# mcu.net
KiCad netlist of a schematic drawn in Altium Designer
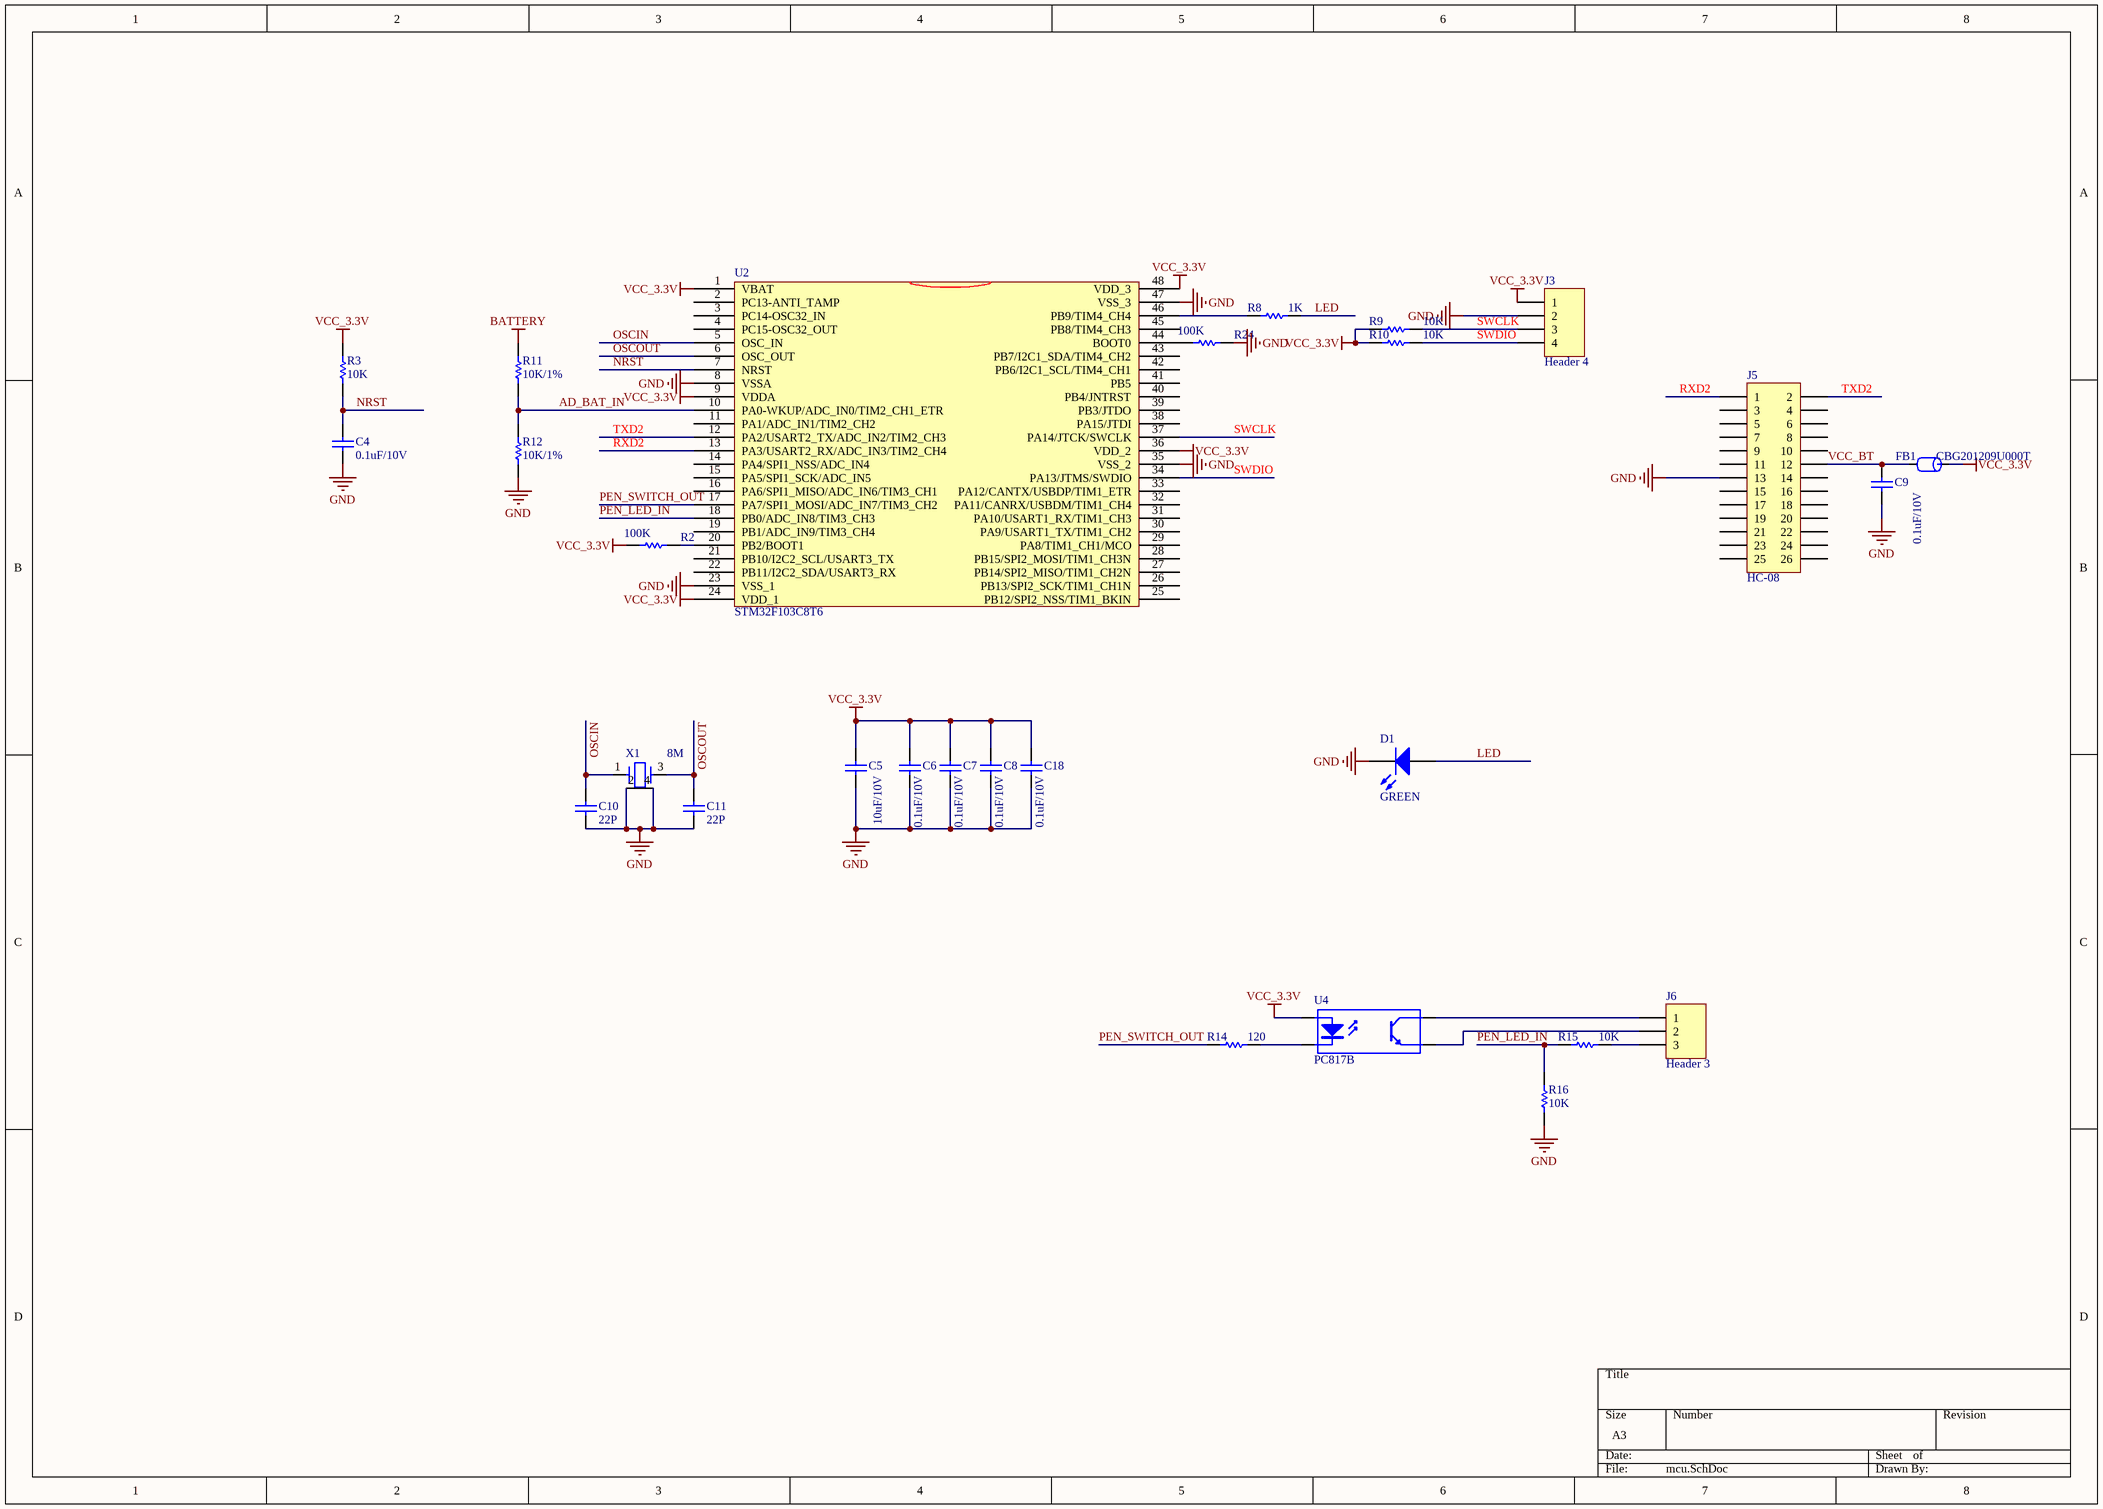
[diagram p0: mcu.SchDoc]

(export (version "E")
  (design (tool "Eeschema 10.0.6"))
  (components
    (comp (ref "C4")
      (value "0.1uF/10V")
      (footprint "0402C")
      (description "Capacitor")
      (fields (field (name "PUBLISHER") "Altium Limited"))
      (libsource (lib "Miscellaneous Devices") (part "Cap"))
    )
    (comp (ref "C5")
      (value "10uF/10V")
      (footprint "0603C")
      (description "Capacitor")
      (fields (field (name "PUBLISHER") "Altium Limited"))
      (libsource (lib "Miscellaneous Devices") (part "Cap"))
    )
    (comp (ref "C6")
      (value "0.1uF/10V")
      (footprint "0402C")
      (description "Capacitor")
      (fields (field (name "PUBLISHER") "Altium Limited"))
      (libsource (lib "Miscellaneous Devices") (part "Cap"))
    )
    (comp (ref "C7")
      (value "0.1uF/10V")
      (footprint "0402C")
      (description "Capacitor")
      (fields (field (name "PUBLISHER") "Altium Limited"))
      (libsource (lib "Miscellaneous Devices") (part "Cap"))
    )
    (comp (ref "C8")
      (value "0.1uF/10V")
      (footprint "0402C")
      (description "Capacitor")
      (fields (field (name "PUBLISHER") "Altium Limited"))
      (libsource (lib "Miscellaneous Devices") (part "Cap"))
    )
    (comp (ref "C9")
      (value "0.1uF/10V")
      (footprint "0402C")
      (description "Capacitor")
      (fields (field (name "PUBLISHER") "Altium Limited"))
      (libsource (lib "Miscellaneous Devices") (part "Cap"))
    )
    (comp (ref "C10")
      (value "22P")
      (footprint "0402C")
      (description "Capacitor")
      (fields (field (name "PUBLISHER") "Altium Limited"))
      (libsource (lib "Miscellaneous Devices") (part "Cap"))
    )
    (comp (ref "C11")
      (value "22P")
      (footprint "0402C")
      (description "Capacitor")
      (fields (field (name "PUBLISHER") "Altium Limited"))
      (libsource (lib "Miscellaneous Devices") (part "Cap"))
    )
    (comp (ref "C18")
      (value "0.1uF/10V")
      (footprint "0402C")
      (description "Capacitor")
      (fields (field (name "PUBLISHER") "Altium Limited"))
      (libsource (lib "Miscellaneous Devices") (part "Cap"))
    )
    (comp (ref "D1")
      (value "~")
      (footprint "0603LED")
      (description "Typical INFRARED GaAs LED")
      (fields (field (name "PUBLISHER") "GREEN"))
      (libsource (lib "Miscellaneous Devices") (part "LED0"))
    )
    (comp (ref "FB1")
      (value "CBG201209U000T")
      (footprint "0805CZ")
      (description "BLM21PG331SN1D")
      (libsource (lib "Schlib_20110825") (part "FB"))
    )
    (comp (ref "J3")
      (value "Header 4")
      (footprint "mHDR1X4")
      (description "Header, 4-Pin")
      (fields (field (name "PUBLISHER") "Altium Limited"))
      (libsource (lib "Miscellaneous Connectors") (part "Header 4"))
    )
    (comp (ref "J5")
      (value "HC-08")
      (footprint "HC-08V20/22/41")
      (description "Header, 13-Pin, Dual row")
      (fields (field (name "PUBLISHER") "Altium Limited"))
      (libsource (lib "Miscellaneous Connectors") (part "Header 13X2"))
    )
    (comp (ref "J6")
      (value "Header 3")
      (footprint "HDR1X3")
      (description "Header, 3-Pin")
      (fields (field (name "PUBLISHER") "Altium Limited"))
      (libsource (lib "Miscellaneous Connectors") (part "Header 3"))
    )
    (comp (ref "R2")
      (value "100K")
      (footprint "0402R")
      (description "Resistor")
      (fields (field (name "PUBLISHER") "Altium Limited"))
      (libsource (lib "Miscellaneous Devices") (part "Res1"))
    )
    (comp (ref "R3")
      (value "10K")
      (footprint "0402R")
      (description "Semiconductor Resistor")
      (fields (field (name "PUBLISHER") "Altium Limited"))
      (libsource (lib "Miscellaneous Devices") (part "Res Semi"))
    )
    (comp (ref "R8")
      (value "1K")
      (footprint "0402R")
      (description "Semiconductor Resistor")
      (fields (field (name "PUBLISHER") "Altium Limited"))
      (libsource (lib "Miscellaneous Devices") (part "Res Semi"))
    )
    (comp (ref "R9")
      (value "10K")
      (footprint "0402R")
      (description "Semiconductor Resistor")
      (fields (field (name "PUBLISHER") "Altium Limited"))
      (libsource (lib "Miscellaneous Devices") (part "Res Semi"))
    )
    (comp (ref "R10")
      (value "10K")
      (footprint "0402R")
      (description "Semiconductor Resistor")
      (fields (field (name "PUBLISHER") "Altium Limited"))
      (libsource (lib "Miscellaneous Devices") (part "Res Semi"))
    )
    (comp (ref "R11")
      (value "10K/1%")
      (footprint "0402R")
      (description "Semiconductor Resistor")
      (fields (field (name "PUBLISHER") "Altium Limited"))
      (libsource (lib "Miscellaneous Devices") (part "Res Semi"))
    )
    (comp (ref "R12")
      (value "10K/1%")
      (footprint "0402R")
      (description "Semiconductor Resistor")
      (fields (field (name "PUBLISHER") "Altium Limited"))
      (libsource (lib "Miscellaneous Devices") (part "Res Semi"))
    )
    (comp (ref "R14")
      (value "120")
      (footprint "0402R")
      (description "Semiconductor Resistor")
      (fields (field (name "PUBLISHER") "Altium Limited"))
      (libsource (lib "Miscellaneous Devices") (part "Res Semi"))
    )
    (comp (ref "R15")
      (value "10K")
      (footprint "0402R")
      (description "Semiconductor Resistor")
      (fields (field (name "PUBLISHER") "Altium Limited"))
      (libsource (lib "Miscellaneous Devices") (part "Res Semi"))
    )
    (comp (ref "R16")
      (value "10K")
      (footprint "0402R")
      (description "Semiconductor Resistor")
      (fields (field (name "PUBLISHER") "Altium Limited"))
      (libsource (lib "Miscellaneous Devices") (part "Res Semi"))
    )
    (comp (ref "R24")
      (value "100K")
      (footprint "0402R")
      (description "Resistor")
      (fields (field (name "PUBLISHER") "Altium Limited"))
      (libsource (lib "Miscellaneous Devices") (part "Res1"))
    )
    (comp (ref "U2")
      (value "STM32F103C8T6")
      (footprint "TQFP-48")
      (libsource (lib "stm32") (part "STM32F103C6"))
    )
    (comp (ref "U4")
      (value "PC817B")
      (footprint "DIP-4")
      (description "4-Pin Phototransistor Optocoupler")
      (fields (field (name "PUBLISHER") "Altium Limited"))
      (libsource (lib "Miscellaneous Devices") (part "Optoisolator1"))
    )
    (comp (ref "X1")
      (value "8M")
      (footprint "XTAL4TN_3225")
      (libsource (lib "Schlib_20110825") (part "CRYSTAL-4"))
    )
  )
  (nets
    (net (code "1") (name "/AD_BAT_IN") (class "Default")
      (node (ref "R11") (pin "2") (pinfunction "2_2") (pintype "passive"))
      (node (ref "R12") (pin "1") (pinfunction "1_1") (pintype "passive"))
      (node (ref "U2") (pin "10") (pinfunction "PA0-WKUP/ADC_IN0/TIM2_CH1_ETR_10") (pintype "passive"))
    )
    (net (code "2") (name "/LED") (class "Default")
      (node (ref "D1") (pin "1") (pinfunction "A_1") (pintype "passive"))
      (node (ref "R8") (pin "2") (pinfunction "2_2") (pintype "passive"))
    )
    (net (code "3") (name "/NRST") (class "Default")
      (node (ref "C4") (pin "2") (pinfunction "2_2") (pintype "passive"))
      (node (ref "R3") (pin "2") (pinfunction "2_2") (pintype "passive"))
      (node (ref "U2") (pin "7") (pinfunction "NRST_7") (pintype "passive"))
    )
    (net (code "4") (name "/OSCIN") (class "Default")
      (node (ref "C10") (pin "2") (pinfunction "2_2") (pintype "passive"))
      (node (ref "U2") (pin "5") (pinfunction "OSC_IN_5") (pintype "passive"))
      (node (ref "X1") (pin "1") (pinfunction "X1_1") (pintype "passive"))
    )
    (net (code "5") (name "/OSCOUT") (class "Default")
      (node (ref "C11") (pin "2") (pinfunction "2_2") (pintype "passive"))
      (node (ref "U2") (pin "6") (pinfunction "OSC_OUT_6") (pintype "passive"))
      (node (ref "X1") (pin "3") (pinfunction "X2_3") (pintype "passive"))
    )
    (net (code "6") (name "/PEN_LED_IN") (class "Default")
      (node (ref "R15") (pin "1") (pinfunction "1_1") (pintype "passive"))
      (node (ref "R16") (pin "2") (pinfunction "2_2") (pintype "passive"))
      (node (ref "U2") (pin "18") (pinfunction "PB0/ADC_IN8/TIM3_CH3_18") (pintype "passive"))
    )
    (net (code "7") (name "/PEN_SWITCH_OUT") (class "Default")
      (node (ref "R14") (pin "1") (pinfunction "1_1") (pintype "passive"))
      (node (ref "U2") (pin "17") (pinfunction "PA7/SPI1_MOSI/ADC_IN7/TIM3_CH2_17") (pintype "passive"))
    )
    (net (code "8") (name "/RXD2") (class "Default")
      (node (ref "J5") (pin "1") (pinfunction "1_1") (pintype "passive"))
      (node (ref "U2") (pin "13") (pinfunction "PA3/USART2_RX/ADC_IN3/TIM2_CH4_13") (pintype "passive"))
    )
    (net (code "9") (name "/SWCLK") (class "Default")
      (node (ref "J3") (pin "3") (pinfunction "3_3") (pintype "passive"))
      (node (ref "R9") (pin "2") (pinfunction "2_2") (pintype "passive"))
      (node (ref "U2") (pin "37") (pinfunction "PA14/JTCK/SWCLK_37") (pintype "passive"))
    )
    (net (code "10") (name "/SWDIO") (class "Default")
      (node (ref "J3") (pin "4") (pinfunction "4_4") (pintype "passive"))
      (node (ref "R10") (pin "2") (pinfunction "2_2") (pintype "passive"))
      (node (ref "U2") (pin "34") (pinfunction "PA13/JTMS/SWDIO_34") (pintype "passive"))
    )
    (net (code "11") (name "/TXD2") (class "Default")
      (node (ref "J5") (pin "2") (pinfunction "2_2") (pintype "passive"))
      (node (ref "U2") (pin "12") (pinfunction "PA2/USART2_TX/ADC_IN2/TIM2_CH3_12") (pintype "passive"))
    )
    (net (code "12") (name "/VCC_BT") (class "Default")
      (node (ref "C9") (pin "2") (pinfunction "2_2") (pintype "passive"))
      (node (ref "FB1") (pin "2") (pintype "passive"))
      (node (ref "J5") (pin "12") (pinfunction "12_12") (pintype "passive"))
    )
    (net (code "13") (name "BATTERY") (class "Default")
      (node (ref "R11") (pin "1") (pinfunction "1_1") (pintype "passive"))
    )
    (net (code "14") (name "GND") (class "Default")
      (node (ref "C10") (pin "1") (pinfunction "1_1") (pintype "passive"))
      (node (ref "C11") (pin "1") (pinfunction "1_1") (pintype "passive"))
      (node (ref "C18") (pin "1") (pinfunction "1_1") (pintype "passive"))
      (node (ref "C4") (pin "1") (pinfunction "1_1") (pintype "passive"))
      (node (ref "C5") (pin "1") (pinfunction "1_1") (pintype "passive"))
      (node (ref "C6") (pin "1") (pinfunction "1_1") (pintype "passive"))
      (node (ref "C7") (pin "1") (pinfunction "1_1") (pintype "passive"))
      (node (ref "C8") (pin "1") (pinfunction "1_1") (pintype "passive"))
      (node (ref "C9") (pin "1") (pinfunction "1_1") (pintype "passive"))
      (node (ref "D1") (pin "2") (pinfunction "K_2") (pintype "passive"))
      (node (ref "J3") (pin "2") (pinfunction "2_2") (pintype "passive"))
      (node (ref "J5") (pin "13") (pinfunction "13_13") (pintype "passive"))
      (node (ref "R12") (pin "2") (pinfunction "2_2") (pintype "passive"))
      (node (ref "R16") (pin "1") (pinfunction "1_1") (pintype "passive"))
      (node (ref "R24") (pin "1") (pinfunction "1_1") (pintype "passive"))
      (node (ref "U2") (pin "23") (pinfunction "VSS_1_23") (pintype "passive"))
      (node (ref "U2") (pin "35") (pinfunction "VSS_2_35") (pintype "passive"))
      (node (ref "U2") (pin "47") (pinfunction "VSS_3_47") (pintype "passive"))
      (node (ref "U2") (pin "8") (pinfunction "VSSA_8") (pintype "passive"))
      (node (ref "X1") (pin "2") (pinfunction "GND_2") (pintype "passive"))
      (node (ref "X1") (pin "4") (pinfunction "GND_4") (pintype "passive"))
    )
    (net (code "15") (name "Net-(J6-Pad3)") (class "Default")
      (node (ref "J6") (pin "3") (pinfunction "3_3") (pintype "passive"))
      (node (ref "R15") (pin "2") (pinfunction "2_2") (pintype "passive"))
    )
    (net (code "16") (name "Net-(U2-BOOT0)") (class "Default")
      (node (ref "R24") (pin "2") (pinfunction "2_2") (pintype "passive"))
      (node (ref "U2") (pin "44") (pinfunction "BOOT0_44") (pintype "passive"))
    )
    (net (code "17") (name "Net-(U2-PB2{slash}BOOT1)") (class "Default")
      (node (ref "R2") (pin "1") (pinfunction "1_1") (pintype "passive"))
      (node (ref "U2") (pin "20") (pinfunction "PB2/BOOT1_20") (pintype "passive"))
    )
    (net (code "18") (name "Net-(U2-PB9{slash}TIM4_CH4)") (class "Default")
      (node (ref "R8") (pin "1") (pinfunction "1_1") (pintype "passive"))
      (node (ref "U2") (pin "46") (pinfunction "PB9/TIM4_CH4_46") (pintype "passive"))
    )
    (net (code "19") (name "Net-(U4-C)") (class "Default")
      (node (ref "J6") (pin "1") (pinfunction "1_1") (pintype "passive"))
      (node (ref "U4") (pin "4") (pinfunction "C_4") (pintype "passive"))
    )
    (net (code "20") (name "Net-(U4-E)") (class "Default")
      (node (ref "J6") (pin "2") (pinfunction "2_2") (pintype "passive"))
      (node (ref "U4") (pin "3") (pinfunction "E_3") (pintype "passive"))
    )
    (net (code "21") (name "Net-(U4-K)") (class "Default")
      (node (ref "R14") (pin "2") (pinfunction "2_2") (pintype "passive"))
      (node (ref "U4") (pin "2") (pinfunction "K_2") (pintype "passive"))
    )
    (net (code "22") (name "VCC_3.3V") (class "Default")
      (node (ref "C18") (pin "2") (pinfunction "2_2") (pintype "passive"))
      (node (ref "C5") (pin "2") (pinfunction "2_2") (pintype "passive"))
      (node (ref "C6") (pin "2") (pinfunction "2_2") (pintype "passive"))
      (node (ref "C7") (pin "2") (pinfunction "2_2") (pintype "passive"))
      (node (ref "C8") (pin "2") (pinfunction "2_2") (pintype "passive"))
      (node (ref "FB1") (pin "1") (pintype "passive"))
      (node (ref "J3") (pin "1") (pinfunction "1_1") (pintype "passive"))
      (node (ref "R10") (pin "1") (pinfunction "1_1") (pintype "passive"))
      (node (ref "R2") (pin "2") (pinfunction "2_2") (pintype "passive"))
      (node (ref "R3") (pin "1") (pinfunction "1_1") (pintype "passive"))
      (node (ref "R9") (pin "1") (pinfunction "1_1") (pintype "passive"))
      (node (ref "U2") (pin "1") (pinfunction "VBAT_1") (pintype "passive"))
      (node (ref "U2") (pin "24") (pinfunction "VDD_1_24") (pintype "passive"))
      (node (ref "U2") (pin "36") (pinfunction "VDD_2_36") (pintype "passive"))
      (node (ref "U2") (pin "48") (pinfunction "VDD_3_48") (pintype "passive"))
      (node (ref "U2") (pin "9") (pinfunction "VDDA_9") (pintype "passive"))
      (node (ref "U4") (pin "1") (pinfunction "A_1") (pintype "passive"))
    )
    (net (code "23") (name "unconnected-(J5-Pad3)") (class "Default")
      (node (ref "J5") (pin "3") (pinfunction "3_3") (pintype "passive"))
    )
    (net (code "24") (name "unconnected-(J5-Pad4)") (class "Default")
      (node (ref "J5") (pin "4") (pinfunction "4_4") (pintype "passive"))
    )
    (net (code "25") (name "unconnected-(J5-Pad5)") (class "Default")
      (node (ref "J5") (pin "5") (pinfunction "5_5") (pintype "passive"))
    )
    (net (code "26") (name "unconnected-(J5-Pad6)") (class "Default")
      (node (ref "J5") (pin "6") (pinfunction "6_6") (pintype "passive"))
    )
    (net (code "27") (name "unconnected-(J5-Pad7)") (class "Default")
      (node (ref "J5") (pin "7") (pinfunction "7_7") (pintype "passive"))
    )
    (net (code "28") (name "unconnected-(J5-Pad8)") (class "Default")
      (node (ref "J5") (pin "8") (pinfunction "8_8") (pintype "passive"))
    )
    (net (code "29") (name "unconnected-(J5-Pad9)") (class "Default")
      (node (ref "J5") (pin "9") (pinfunction "9_9") (pintype "passive"))
    )
    (net (code "30") (name "unconnected-(J5-Pad10)") (class "Default")
      (node (ref "J5") (pin "10") (pinfunction "10_10") (pintype "passive"))
    )
    (net (code "31") (name "unconnected-(J5-Pad11)") (class "Default")
      (node (ref "J5") (pin "11") (pinfunction "11_11") (pintype "passive"))
    )
    (net (code "32") (name "unconnected-(J5-Pad14)") (class "Default")
      (node (ref "J5") (pin "14") (pinfunction "14_14") (pintype "passive"))
    )
    (net (code "33") (name "unconnected-(J5-Pad15)") (class "Default")
      (node (ref "J5") (pin "15") (pinfunction "15_15") (pintype "passive"))
    )
    (net (code "34") (name "unconnected-(J5-Pad16)") (class "Default")
      (node (ref "J5") (pin "16") (pinfunction "16_16") (pintype "passive"))
    )
    (net (code "35") (name "unconnected-(J5-Pad17)") (class "Default")
      (node (ref "J5") (pin "17") (pinfunction "17_17") (pintype "passive"))
    )
    (net (code "36") (name "unconnected-(J5-Pad18)") (class "Default")
      (node (ref "J5") (pin "18") (pinfunction "18_18") (pintype "passive"))
    )
    (net (code "37") (name "unconnected-(J5-Pad19)") (class "Default")
      (node (ref "J5") (pin "19") (pinfunction "19_19") (pintype "passive"))
    )
    (net (code "38") (name "unconnected-(J5-Pad20)") (class "Default")
      (node (ref "J5") (pin "20") (pinfunction "20_20") (pintype "passive"))
    )
    (net (code "39") (name "unconnected-(J5-Pad21)") (class "Default")
      (node (ref "J5") (pin "21") (pinfunction "21_21") (pintype "passive"))
    )
    (net (code "40") (name "unconnected-(J5-Pad22)") (class "Default")
      (node (ref "J5") (pin "22") (pinfunction "22_22") (pintype "passive"))
    )
    (net (code "41") (name "unconnected-(J5-Pad23)") (class "Default")
      (node (ref "J5") (pin "23") (pinfunction "23_23") (pintype "passive"))
    )
    (net (code "42") (name "unconnected-(J5-Pad24)") (class "Default")
      (node (ref "J5") (pin "24") (pinfunction "24_24") (pintype "passive"))
    )
    (net (code "43") (name "unconnected-(J5-Pad25)") (class "Default")
      (node (ref "J5") (pin "25") (pinfunction "25_25") (pintype "passive"))
    )
    (net (code "44") (name "unconnected-(J5-Pad26)") (class "Default")
      (node (ref "J5") (pin "26") (pinfunction "26_26") (pintype "passive"))
    )
    (net (code "45") (name "unconnected-(U2-PA1{slash}ADC_IN1{slash}TIM2_CH2-Pad11)") (class "Default")
      (node (ref "U2") (pin "11") (pinfunction "PA1/ADC_IN1/TIM2_CH2_11") (pintype "passive"))
    )
    (net (code "46") (name "unconnected-(U2-PA4{slash}SPI1_NSS{slash}ADC_IN4-Pad14)") (class "Default")
      (node (ref "U2") (pin "14") (pinfunction "PA4/SPI1_NSS/ADC_IN4_14") (pintype "passive"))
    )
    (net (code "47") (name "unconnected-(U2-PA5{slash}SPI1_SCK{slash}ADC_IN5-Pad15)") (class "Default")
      (node (ref "U2") (pin "15") (pinfunction "PA5/SPI1_SCK/ADC_IN5_15") (pintype "passive"))
    )
    (net (code "48") (name "unconnected-(U2-PA6{slash}SPI1_MISO{slash}ADC_IN6{slash}TIM3_CH1-Pad16)") (class "Default")
      (node (ref "U2") (pin "16") (pinfunction "PA6/SPI1_MISO/ADC_IN6/TIM3_CH1_16") (pintype "passive"))
    )
    (net (code "49") (name "unconnected-(U2-PA8{slash}TIM1_CH1{slash}MCO-Pad29)") (class "Default")
      (node (ref "U2") (pin "29") (pinfunction "PA8/TIM1_CH1/MCO_29") (pintype "passive"))
    )
    (net (code "50") (name "unconnected-(U2-PA9{slash}USART1_TX{slash}TIM1_CH2-Pad30)") (class "Default")
      (node (ref "U2") (pin "30") (pinfunction "PA9/USART1_TX/TIM1_CH2_30") (pintype "passive"))
    )
    (net (code "51") (name "unconnected-(U2-PA10{slash}USART1_RX{slash}TIM1_CH3-Pad31)") (class "Default")
      (node (ref "U2") (pin "31") (pinfunction "PA10/USART1_RX/TIM1_CH3_31") (pintype "passive"))
    )
    (net (code "52") (name "unconnected-(U2-PA11{slash}CANRX{slash}USBDM{slash}TIM1_CH4-Pad32)") (class "Default")
      (node (ref "U2") (pin "32") (pinfunction "PA11/CANRX/USBDM/TIM1_CH4_32") (pintype "passive"))
    )
    (net (code "53") (name "unconnected-(U2-PA12{slash}CANTX{slash}USBDP{slash}TIM1_ETR-Pad33)") (class "Default")
      (node (ref "U2") (pin "33") (pinfunction "PA12/CANTX/USBDP/TIM1_ETR_33") (pintype "passive"))
    )
    (net (code "54") (name "unconnected-(U2-PA15{slash}JTDI-Pad38)") (class "Default")
      (node (ref "U2") (pin "38") (pinfunction "PA15/JTDI_38") (pintype "passive"))
    )
    (net (code "55") (name "unconnected-(U2-PB1{slash}ADC_IN9{slash}TIM3_CH4-Pad19)") (class "Default")
      (node (ref "U2") (pin "19") (pinfunction "PB1/ADC_IN9/TIM3_CH4_19") (pintype "passive"))
    )
    (net (code "56") (name "unconnected-(U2-PB3{slash}JTDO-Pad39)") (class "Default")
      (node (ref "U2") (pin "39") (pinfunction "PB3/JTDO_39") (pintype "passive"))
    )
    (net (code "57") (name "unconnected-(U2-PB4{slash}JNTRST-Pad40)") (class "Default")
      (node (ref "U2") (pin "40") (pinfunction "PB4/JNTRST_40") (pintype "passive"))
    )
    (net (code "58") (name "unconnected-(U2-PB5-Pad41)") (class "Default")
      (node (ref "U2") (pin "41") (pinfunction "PB5_41") (pintype "passive"))
    )
    (net (code "59") (name "unconnected-(U2-PB6{slash}I2C1_SCL{slash}TIM4_CH1-Pad42)") (class "Default")
      (node (ref "U2") (pin "42") (pinfunction "PB6/I2C1_SCL/TIM4_CH1_42") (pintype "passive"))
    )
    (net (code "60") (name "unconnected-(U2-PB7{slash}I2C1_SDA{slash}TIM4_CH2-Pad43)") (class "Default")
      (node (ref "U2") (pin "43") (pinfunction "PB7/I2C1_SDA/TIM4_CH2_43") (pintype "passive"))
    )
    (net (code "61") (name "unconnected-(U2-PB8{slash}TIM4_CH3-Pad45)") (class "Default")
      (node (ref "U2") (pin "45") (pinfunction "PB8/TIM4_CH3_45") (pintype "passive"))
    )
    (net (code "62") (name "unconnected-(U2-PB10{slash}I2C2_SCL{slash}USART3_TX-Pad21)") (class "Default")
      (node (ref "U2") (pin "21") (pinfunction "PB10/I2C2_SCL/USART3_TX_21") (pintype "passive"))
    )
    (net (code "63") (name "unconnected-(U2-PB11{slash}I2C2_SDA{slash}USART3_RX-Pad22)") (class "Default")
      (node (ref "U2") (pin "22") (pinfunction "PB11/I2C2_SDA/USART3_RX_22") (pintype "passive"))
    )
    (net (code "64") (name "unconnected-(U2-PB12{slash}SPI2_NSS{slash}TIM1_BKIN-Pad25)") (class "Default")
      (node (ref "U2") (pin "25") (pinfunction "PB12/SPI2_NSS/TIM1_BKIN_25") (pintype "passive"))
    )
    (net (code "65") (name "unconnected-(U2-PB13{slash}SPI2_SCK{slash}TIM1_CH1N-Pad26)") (class "Default")
      (node (ref "U2") (pin "26") (pinfunction "PB13/SPI2_SCK/TIM1_CH1N_26") (pintype "passive"))
    )
    (net (code "66") (name "unconnected-(U2-PB14{slash}SPI2_MISO{slash}TIM1_CH2N-Pad27)") (class "Default")
      (node (ref "U2") (pin "27") (pinfunction "PB14/SPI2_MISO/TIM1_CH2N_27") (pintype "passive"))
    )
    (net (code "67") (name "unconnected-(U2-PB15{slash}SPI2_MOSI{slash}TIM1_CH3N-Pad28)") (class "Default")
      (node (ref "U2") (pin "28") (pinfunction "PB15/SPI2_MOSI/TIM1_CH3N_28") (pintype "passive"))
    )
    (net (code "68") (name "unconnected-(U2-PC13-ANTI_TAMP-Pad2)") (class "Default")
      (node (ref "U2") (pin "2") (pinfunction "PC13-ANTI_TAMP_2") (pintype "passive"))
    )
    (net (code "69") (name "unconnected-(U2-PC14-OSC32_IN-Pad3)") (class "Default")
      (node (ref "U2") (pin "3") (pinfunction "PC14-OSC32_IN_3") (pintype "passive"))
    )
    (net (code "70") (name "unconnected-(U2-PC15-OSC32_OUT-Pad4)") (class "Default")
      (node (ref "U2") (pin "4") (pinfunction "PC15-OSC32_OUT_4") (pintype "passive"))
    )
  )
)
